# FPGA.net
KiCad netlist of a schematic drawn in Altium Designer
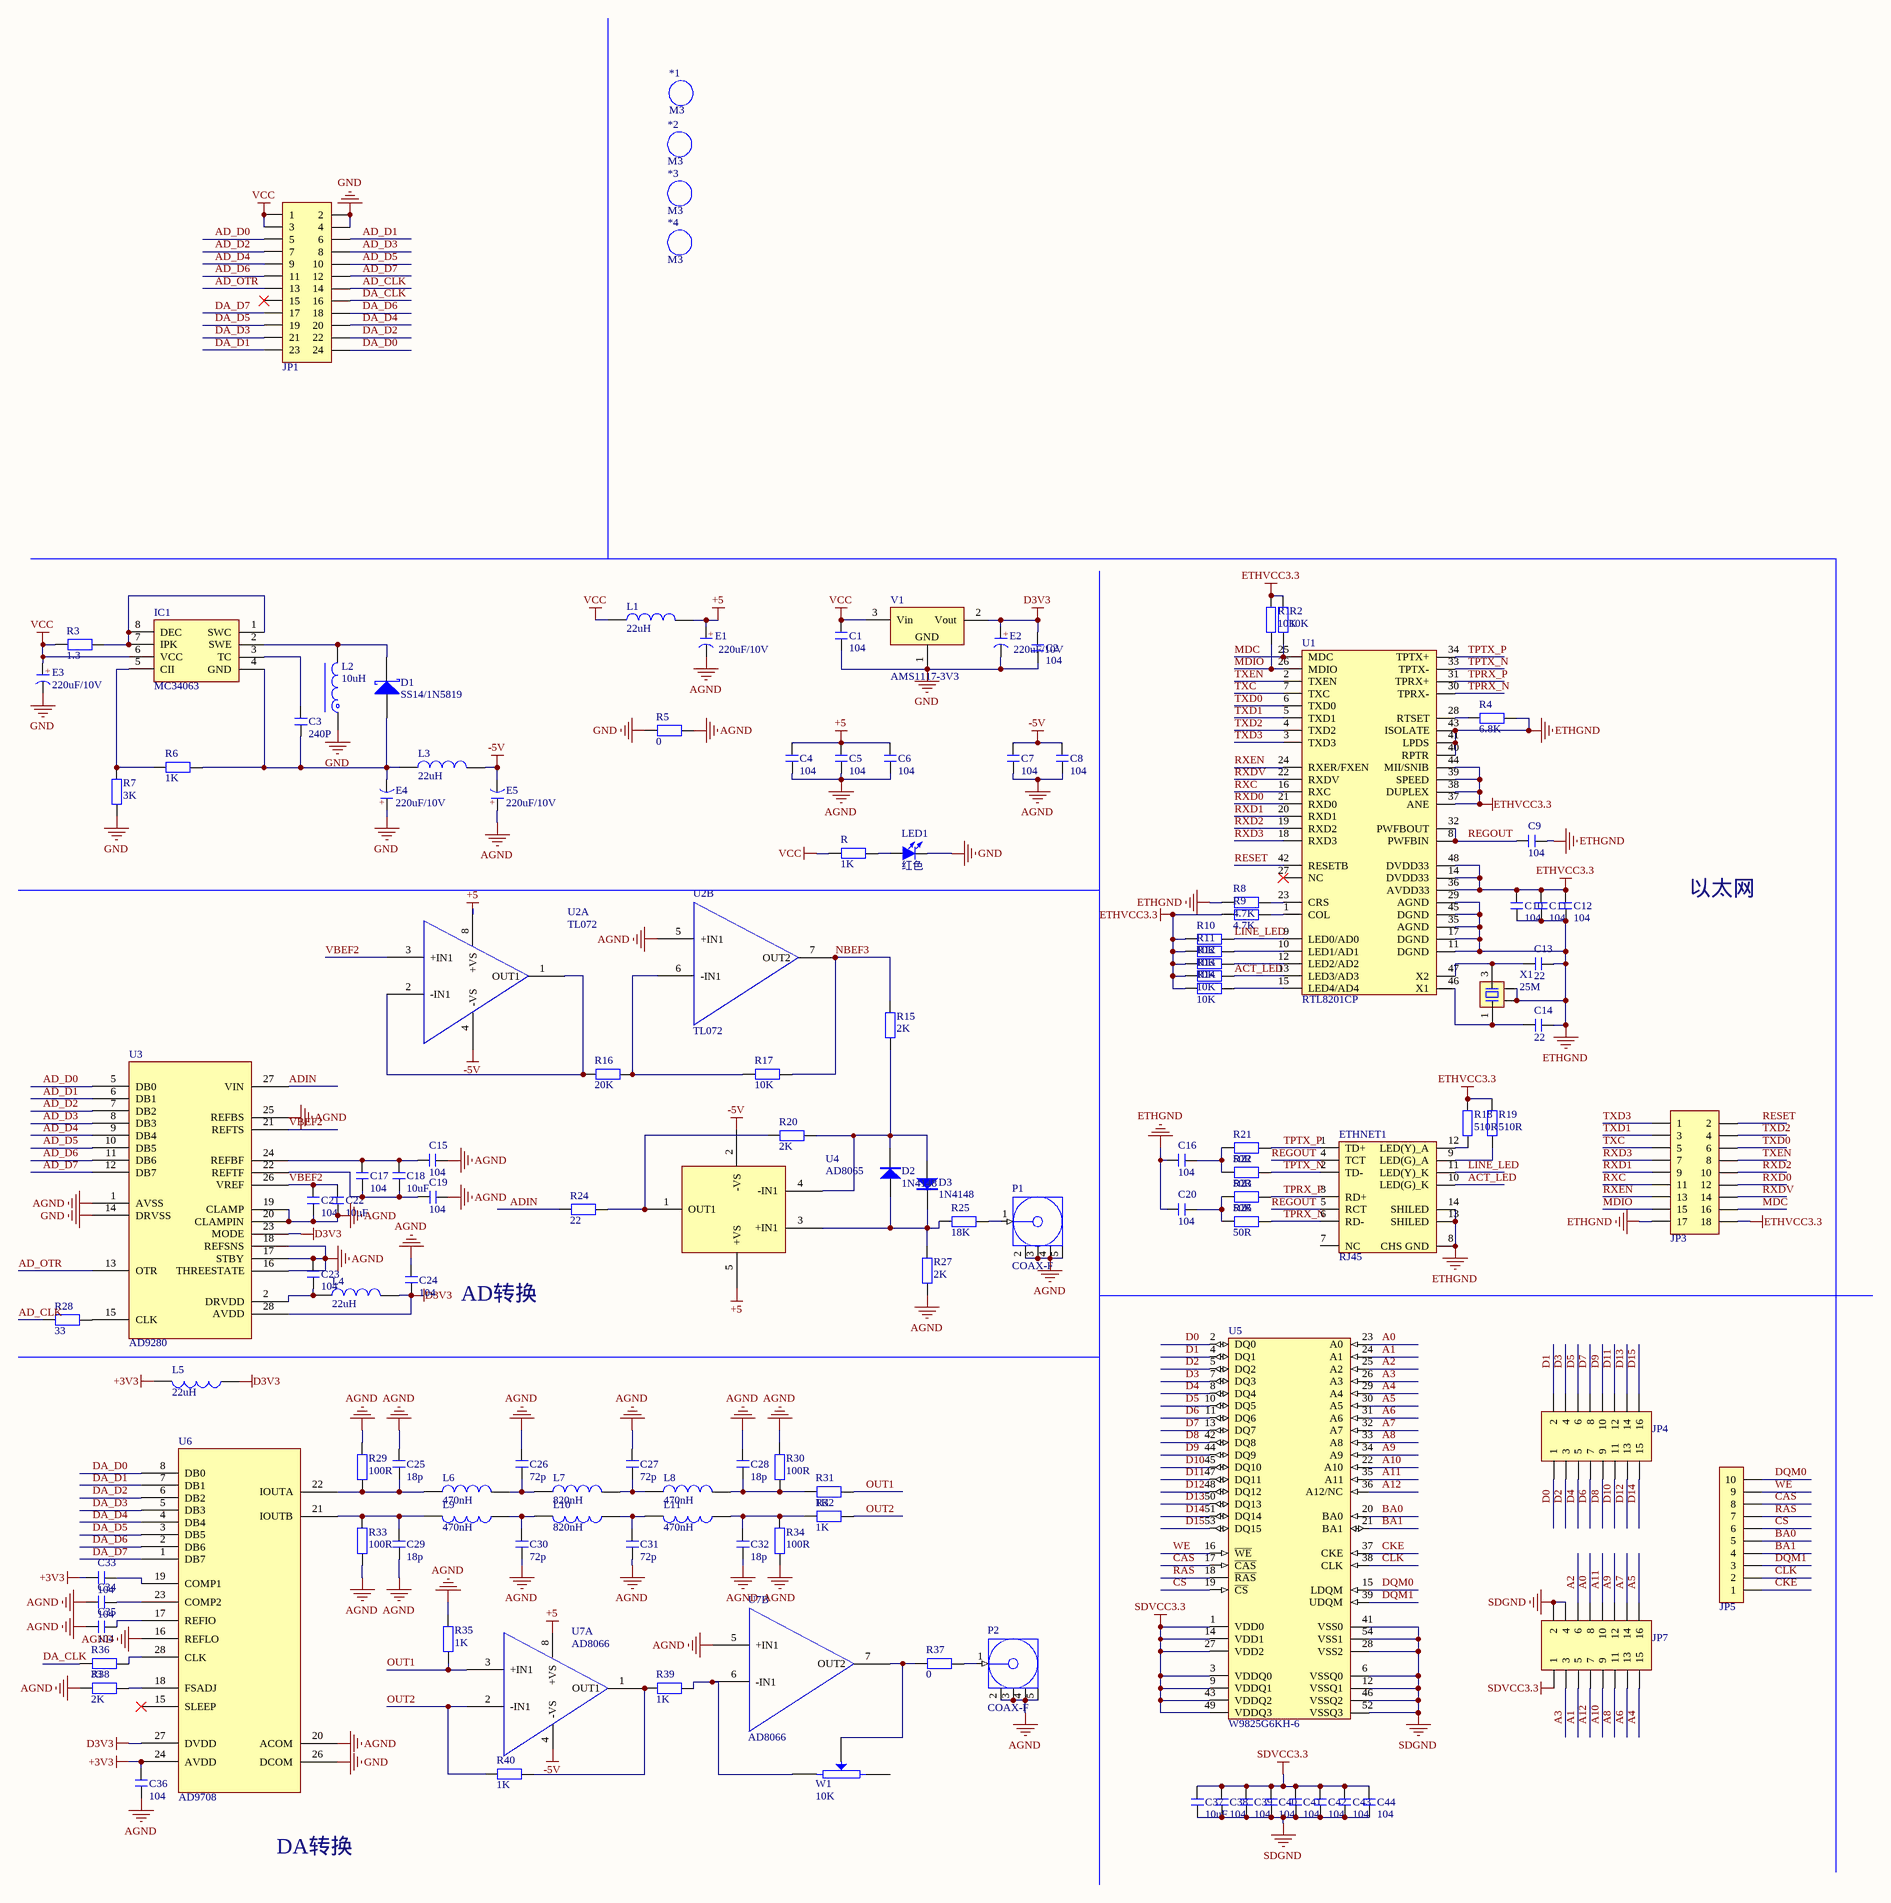
[diagram p0: FPGA扩展板.SchDoc]

(export (version "E")
  (design (tool "Eeschema 10.0.6"))
  (components
    (comp (ref "*1")
      (value "M3")
      (footprint "M3 125X300")
      (description "铜柱孔")
      (fields (field (name "版权归属") "封装库来自淘宝 ID：黄晶宝石"))
      (libsource (lib "4.1 - 未分类器件") (part "M3"))
    )
    (comp (ref "*2")
      (value "M3")
      (footprint "M3 125X300")
      (description "铜柱孔")
      (fields (field (name "版权归属") "封装库来自淘宝 ID：黄晶宝石"))
      (libsource (lib "4.1 - 未分类器件") (part "M3"))
    )
    (comp (ref "*3")
      (value "M3")
      (footprint "M3 125X300")
      (description "铜柱孔")
      (fields (field (name "版权归属") "封装库来自淘宝 ID：黄晶宝石"))
      (libsource (lib "4.1 - 未分类器件") (part "M3"))
    )
    (comp (ref "*4")
      (value "M3")
      (footprint "M3 125X300")
      (description "铜柱孔")
      (fields (field (name "版权归属") "封装库来自淘宝 ID：黄晶宝石"))
      (libsource (lib "4.1 - 未分类器件") (part "M3"))
    )
    (comp (ref "C1")
      (value "104")
      (footprint "C 0805_L")
      (description "贴片电容")
      (libsource (lib "0.1 - 电阻-电容-电感") (part "C"))
    )
    (comp (ref "C2")
      (value "104")
      (footprint "C 0805_L")
      (description "贴片电容")
      (libsource (lib "0.1 - 电阻-电容-电感") (part "C"))
    )
    (comp (ref "C3")
      (value "240P")
      (footprint "C 0805_L")
      (description "贴片电容")
      (libsource (lib "0.1 - 电阻-电容-电感") (part "C"))
    )
    (comp (ref "C4")
      (value "104")
      (footprint "C 0805_L")
      (description "贴片电容")
      (libsource (lib "0.1 - 电阻-电容-电感") (part "C"))
    )
    (comp (ref "C5")
      (value "104")
      (footprint "C 0805_L")
      (description "贴片电容")
      (libsource (lib "0.1 - 电阻-电容-电感") (part "C"))
    )
    (comp (ref "C6")
      (value "104")
      (footprint "C 0805_L")
      (description "贴片电容")
      (libsource (lib "0.1 - 电阻-电容-电感") (part "C"))
    )
    (comp (ref "C7")
      (value "104")
      (footprint "C 0805_L")
      (description "贴片电容")
      (libsource (lib "0.1 - 电阻-电容-电感") (part "C"))
    )
    (comp (ref "C8")
      (value "104")
      (footprint "C 0805_L")
      (description "贴片电容")
      (libsource (lib "0.1 - 电阻-电容-电感") (part "C"))
    )
    (comp (ref "C9")
      (value "104")
      (footprint "C 0805_L")
      (description "贴片电容")
      (libsource (lib "0.1 - 电阻-电容-电感") (part "C"))
    )
    (comp (ref "C10")
      (value "104")
      (footprint "C 0805_L")
      (description "贴片电容")
      (libsource (lib "0.1 - 电阻-电容-电感") (part "C"))
    )
    (comp (ref "C11")
      (value "104")
      (footprint "C 0805_L")
      (description "贴片电容")
      (libsource (lib "0.1 - 电阻-电容-电感") (part "C"))
    )
    (comp (ref "C12")
      (value "104")
      (footprint "C 0805_L")
      (description "贴片电容")
      (libsource (lib "0.1 - 电阻-电容-电感") (part "C"))
    )
    (comp (ref "C13")
      (value "22")
      (footprint "C 0805_L")
      (description "贴片电容")
      (libsource (lib "0.1 - 电阻-电容-电感") (part "C"))
    )
    (comp (ref "C14")
      (value "22")
      (footprint "C 0805_L")
      (description "贴片电容")
      (libsource (lib "0.1 - 电阻-电容-电感") (part "C"))
    )
    (comp (ref "C15")
      (value "104")
      (footprint "C 0805_L")
      (description "贴片电容")
      (libsource (lib "0.1 - 电阻-电容-电感") (part "C"))
    )
    (comp (ref "C16")
      (value "104")
      (footprint "C 0805_L")
      (description "贴片电容")
      (libsource (lib "0.1 - 电阻-电容-电感") (part "C"))
    )
    (comp (ref "C17")
      (value "104")
      (footprint "C 0805_L")
      (description "贴片电容")
      (libsource (lib "0.1 - 电阻-电容-电感") (part "C"))
    )
    (comp (ref "C18")
      (value "10uF")
      (footprint "C 0805_L")
      (description "贴片电容")
      (libsource (lib "0.1 - 电阻-电容-电感") (part "C"))
    )
    (comp (ref "C19")
      (value "104")
      (footprint "C 0805_L")
      (description "贴片电容")
      (libsource (lib "0.1 - 电阻-电容-电感") (part "C"))
    )
    (comp (ref "C20")
      (value "104")
      (footprint "C 0805_L")
      (description "贴片电容")
      (libsource (lib "0.1 - 电阻-电容-电感") (part "C"))
    )
    (comp (ref "C21")
      (value "104")
      (footprint "C 0805_L")
      (description "贴片电容")
      (libsource (lib "0.1 - 电阻-电容-电感") (part "C"))
    )
    (comp (ref "C22")
      (value "10uF")
      (footprint "C 0805_L")
      (description "贴片电容")
      (libsource (lib "0.1 - 电阻-电容-电感") (part "C"))
    )
    (comp (ref "C23")
      (value "104")
      (footprint "C 0805_L")
      (description "贴片电容")
      (libsource (lib "0.1 - 电阻-电容-电感") (part "C"))
    )
    (comp (ref "C24")
      (value "104")
      (footprint "C 0805_L")
      (description "贴片电容")
      (libsource (lib "0.1 - 电阻-电容-电感") (part "C"))
    )
    (comp (ref "C25")
      (value "18p")
      (footprint "C 0805_L")
      (description "贴片电容")
      (libsource (lib "0.1 - 电阻-电容-电感") (part "C"))
    )
    (comp (ref "C26")
      (value "72p")
      (footprint "C 0805_L")
      (description "贴片电容")
      (libsource (lib "0.1 - 电阻-电容-电感") (part "C"))
    )
    (comp (ref "C27")
      (value "72p")
      (footprint "C 0805_L")
      (description "贴片电容")
      (libsource (lib "0.1 - 电阻-电容-电感") (part "C"))
    )
    (comp (ref "C28")
      (value "18p")
      (footprint "C 0805_L")
      (description "贴片电容")
      (libsource (lib "0.1 - 电阻-电容-电感") (part "C"))
    )
    (comp (ref "C29")
      (value "18p")
      (footprint "C 0805_L")
      (description "贴片电容")
      (libsource (lib "0.1 - 电阻-电容-电感") (part "C"))
    )
    (comp (ref "C30")
      (value "72p")
      (footprint "C 0805_L")
      (description "贴片电容")
      (libsource (lib "0.1 - 电阻-电容-电感") (part "C"))
    )
    (comp (ref "C31")
      (value "72p")
      (footprint "C 0805_L")
      (description "贴片电容")
      (libsource (lib "0.1 - 电阻-电容-电感") (part "C"))
    )
    (comp (ref "C32")
      (value "18p")
      (footprint "C 0805_L")
      (description "贴片电容")
      (libsource (lib "0.1 - 电阻-电容-电感") (part "C"))
    )
    (comp (ref "C33")
      (value "104")
      (footprint "C 0805_L")
      (description "贴片电容")
      (libsource (lib "0.1 - 电阻-电容-电感") (part "C"))
    )
    (comp (ref "C34")
      (value "104")
      (footprint "C 0805_L")
      (description "贴片电容")
      (libsource (lib "0.1 - 电阻-电容-电感") (part "C"))
    )
    (comp (ref "C35")
      (value "104")
      (footprint "C 0805_L")
      (description "贴片电容")
      (libsource (lib "0.1 - 电阻-电容-电感") (part "C"))
    )
    (comp (ref "C36")
      (value "104")
      (footprint "C 0805_L")
      (description "贴片电容")
      (libsource (lib "0.1 - 电阻-电容-电感") (part "C"))
    )
    (comp (ref "C37")
      (value "10uF")
      (footprint "C 0805_L")
      (description "贴片电容")
      (libsource (lib "0.1 - 电阻-电容-电感") (part "C"))
    )
    (comp (ref "C38")
      (value "104")
      (footprint "C 0805_L")
      (description "贴片电容")
      (libsource (lib "0.1 - 电阻-电容-电感") (part "C"))
    )
    (comp (ref "C39")
      (value "104")
      (footprint "C 0805_L")
      (description "贴片电容")
      (libsource (lib "0.1 - 电阻-电容-电感") (part "C"))
    )
    (comp (ref "C40")
      (value "104")
      (footprint "C 0805_L")
      (description "贴片电容")
      (libsource (lib "0.1 - 电阻-电容-电感") (part "C"))
    )
    (comp (ref "C41")
      (value "104")
      (footprint "C 0805_L")
      (description "贴片电容")
      (libsource (lib "0.1 - 电阻-电容-电感") (part "C"))
    )
    (comp (ref "C42")
      (value "104")
      (footprint "C 0805_L")
      (description "贴片电容")
      (libsource (lib "0.1 - 电阻-电容-电感") (part "C"))
    )
    (comp (ref "C43")
      (value "104")
      (footprint "C 0805_L")
      (description "贴片电容")
      (libsource (lib "0.1 - 电阻-电容-电感") (part "C"))
    )
    (comp (ref "C44")
      (value "104")
      (footprint "C 0805_L")
      (description "贴片电容")
      (libsource (lib "0.1 - 电阻-电容-电感") (part "C"))
    )
    (comp (ref "D1")
      (value "SS14/1N5819")
      (footprint "SMA")
      (description "肖特基二极管")
      (libsource (lib "0.2 -  二极管-整流桥") (part "SS14"))
    )
    (comp (ref "D2")
      (value "1N4148")
      (footprint "MINI_MELF (LL34)")
      (description "开关二极管")
      (libsource (lib "0.2 -  二极管-整流桥") (part "1N4148"))
    )
    (comp (ref "D3")
      (value "1N4148")
      (footprint "MINI_MELF (LL34)")
      (description "开关二极管")
      (libsource (lib "0.2 -  二极管-整流桥") (part "1N4148"))
    )
    (comp (ref "E1")
      (value "220uF/10V")
      (footprint "CM D(6.3*5.4)")
      (description "贴片电解电容")
      (fields (field (name "版权归属") "封装库来自淘宝 ID：黄晶宝石"))
      (libsource (lib "0.1 - 电阻-电容-电感") (part "CE_SMD"))
    )
    (comp (ref "E2")
      (value "220uF/10V")
      (footprint "CM D(6.3*5.4)")
      (description "贴片电解电容")
      (fields (field (name "版权归属") "封装库来自淘宝 ID：黄晶宝石"))
      (libsource (lib "0.1 - 电阻-电容-电感") (part "CE_SMD"))
    )
    (comp (ref "E3")
      (value "220uF/10V")
      (footprint "CM D(6.3*5.4)")
      (description "贴片电解电容")
      (fields (field (name "版权归属") "封装库来自淘宝 ID：黄晶宝石"))
      (libsource (lib "0.1 - 电阻-电容-电感") (part "CE_SMD"))
    )
    (comp (ref "E4")
      (value "220uF/10V")
      (footprint "CM D(6.3*5.4)")
      (description "贴片电解电容")
      (fields (field (name "版权归属") "封装库来自淘宝 ID：黄晶宝石"))
      (libsource (lib "0.1 - 电阻-电容-电感") (part "CE_SMD"))
    )
    (comp (ref "E5")
      (value "220uF/10V")
      (footprint "CM D(6.3*5.4)")
      (description "贴片电解电容")
      (fields (field (name "版权归属") "封装库来自淘宝 ID：黄晶宝石"))
      (libsource (lib "0.1 - 电阻-电容-电感") (part "CE_SMD"))
    )
    (comp (ref "ETHNET1")
      (value "RJ45")
      (footprint "HR911105A")
      (libsource (lib "PIONEER") (part "HR911105"))
    )
    (comp (ref "IC1")
      (value "MC34063")
      (footprint "SOP8_N")
      (description "DC升降压芯片")
      (fields (field (name "版权归属") "封装库来自淘宝 ID：黄晶宝石"))
      (libsource (lib "1.1 - 电源类芯片") (part "MC34063"))
    )
    (comp (ref "JP1")
      (value "Header 2X11")
      (footprint "HDR2.54-LI-2x12P")
      (description "12*2P接插件")
      (fields (field (name "版权归属") "源创客"))
      (libsource (lib "5.3 - 接插件-脚距2.54 (100mil) ") (part "Header 12X2"))
    )
    (comp (ref "JP3")
      (value "Header 9X2")
      (footprint "HDR2.54-LI-2x9P")
      (description "9*2P接插件")
      (fields (field (name "版权归属") "源创客"))
      (libsource (lib "5.3 - 接插件-脚距2.54 (100mil) ") (part "Header 9X2"))
    )
    (comp (ref "JP4")
      (value "Header 8X2")
      (footprint "HDR2.54-LI-2x8P")
      (description "8*2P接插件")
      (fields (field (name "版权归属") "封装库来自淘宝 ID：黄晶宝石"))
      (libsource (lib "5.3 - 接插件-脚距2.54 (100mil) ") (part "Header 8X2"))
    )
    (comp (ref "JP5")
      (value "HDR-1X10")
      (footprint "HDR2.54-LI-10P")
      (description "10P接插件")
      (fields (field (name "版权归属") "源创客"))
      (libsource (lib "5.3 - 接插件-脚距2.54 (100mil) ") (part "Header 10"))
    )
    (comp (ref "JP7")
      (value "Header 8X2")
      (footprint "HDR2.54-LI-2x8P")
      (description "8*2P接插件")
      (fields (field (name "版权归属") "封装库来自淘宝 ID：黄晶宝石"))
      (libsource (lib "5.3 - 接插件-脚距2.54 (100mil) ") (part "Header 8X2"))
    )
    (comp (ref "L1")
      (value "22uH")
      (footprint "L 0805")
      (description "小功率贴片电感")
      (libsource (lib "0.1 - 电阻-电容-电感") (part "L"))
    )
    (comp (ref "L2")
      (value "10uH")
      (footprint "CDRH73")
      (description "功率屏蔽电感")
      (fields (field (name "版权归属") "封装库来自淘宝 ID：黄晶宝石"))
      (libsource (lib "0.1 - 电阻-电容-电感") (part "L-CDRH"))
    )
    (comp (ref "L3")
      (value "22uH")
      (footprint "L 0805")
      (description "小功率贴片电感")
      (libsource (lib "0.1 - 电阻-电容-电感") (part "L"))
    )
    (comp (ref "L4")
      (value "22uH")
      (footprint "L 0805")
      (description "小功率贴片电感")
      (libsource (lib "0.1 - 电阻-电容-电感") (part "L"))
    )
    (comp (ref "L5")
      (value "22uH")
      (footprint "L 0805")
      (description "小功率贴片电感")
      (libsource (lib "0.1 - 电阻-电容-电感") (part "L"))
    )
    (comp (ref "L6")
      (value "470nH")
      (footprint "L 0805")
      (description "小功率贴片电感")
      (libsource (lib "0.1 - 电阻-电容-电感") (part "L"))
    )
    (comp (ref "L7")
      (value "820nH")
      (footprint "L 0805")
      (description "小功率贴片电感")
      (libsource (lib "0.1 - 电阻-电容-电感") (part "L"))
    )
    (comp (ref "L8")
      (value "470nH")
      (footprint "L 0805")
      (description "小功率贴片电感")
      (libsource (lib "0.1 - 电阻-电容-电感") (part "L"))
    )
    (comp (ref "L9")
      (value "470nH")
      (footprint "L 0805")
      (description "小功率贴片电感")
      (libsource (lib "0.1 - 电阻-电容-电感") (part "L"))
    )
    (comp (ref "L10")
      (value "820nH")
      (footprint "L 0805")
      (description "小功率贴片电感")
      (libsource (lib "0.1 - 电阻-电容-电感") (part "L"))
    )
    (comp (ref "L11")
      (value "470nH")
      (footprint "L 0805")
      (description "小功率贴片电感")
      (libsource (lib "0.1 - 电阻-电容-电感") (part "L"))
    )
    (comp (ref "LED1")
      (value "红色")
      (footprint "LED 0805B")
      (description "贴片LED")
      (fields (field (name "版权归属") "封装库来自淘宝 ID：黄晶宝石"))
      (libsource (lib "0.3 - LED发光二极管") (part "LED-SMD"))
    )
    (comp (ref "P1")
      (value "COAX-F")
      (footprint "MCX5.08-H5")
      (fields (field (name "PUBLISHER") "Altium Limited"))
      (libsource (lib "HS_AD_DA_V2.3") (part "COAX-F"))
    )
    (comp (ref "P2")
      (value "COAX-F")
      (footprint "MCX5.08-H5")
      (fields (field (name "PUBLISHER") "Altium Limited"))
      (libsource (lib "HS_AD_DA_V2.3") (part "COAX-F"))
    )
    (comp (ref "R")
      (value "1K")
      (footprint "R 0805_L")
      (description "贴片电阻")
      (fields (field (name "版权归属") "来自淘宝 ID：黄晶宝石"))
      (libsource (lib "0.1 - 电阻-电容-电感") (part "R"))
    )
    (comp (ref "R1")
      (value "10K")
      (footprint "R 0805_L")
      (description "贴片电阻")
      (fields (field (name "版权归属") "来自淘宝 ID：黄晶宝石"))
      (libsource (lib "0.1 - 电阻-电容-电感") (part "R"))
    )
    (comp (ref "R2")
      (value "10K")
      (footprint "R 0805_L")
      (description "贴片电阻")
      (fields (field (name "版权归属") "来自淘宝 ID：黄晶宝石"))
      (libsource (lib "0.1 - 电阻-电容-电感") (part "R"))
    )
    (comp (ref "R3")
      (value "1.3")
      (footprint "R 0805_L")
      (description "贴片电阻")
      (fields (field (name "版权归属") "来自淘宝 ID：黄晶宝石"))
      (libsource (lib "0.1 - 电阻-电容-电感") (part "R"))
    )
    (comp (ref "R4")
      (value "6.8K")
      (footprint "R 0805_L")
      (description "贴片电阻")
      (fields (field (name "版权归属") "来自淘宝 ID：黄晶宝石"))
      (libsource (lib "0.1 - 电阻-电容-电感") (part "R"))
    )
    (comp (ref "R5")
      (value "0")
      (footprint "R 0805_L")
      (description "贴片电阻")
      (fields (field (name "版权归属") "来自淘宝 ID：黄晶宝石"))
      (libsource (lib "0.1 - 电阻-电容-电感") (part "R"))
    )
    (comp (ref "R6")
      (value "1K")
      (footprint "R 0805_L")
      (description "贴片电阻")
      (fields (field (name "版权归属") "来自淘宝 ID：黄晶宝石"))
      (libsource (lib "0.1 - 电阻-电容-电感") (part "R"))
    )
    (comp (ref "R7")
      (value "3K")
      (footprint "R 0805_L")
      (description "贴片电阻")
      (fields (field (name "版权归属") "来自淘宝 ID：黄晶宝石"))
      (libsource (lib "0.1 - 电阻-电容-电感") (part "R"))
    )
    (comp (ref "R8")
      (value "4.7K")
      (footprint "R 0805_L")
      (description "贴片电阻")
      (fields (field (name "版权归属") "来自淘宝 ID：黄晶宝石"))
      (libsource (lib "0.1 - 电阻-电容-电感") (part "R"))
    )
    (comp (ref "R9")
      (value "4.7K")
      (footprint "R 0805_L")
      (description "贴片电阻")
      (fields (field (name "版权归属") "来自淘宝 ID：黄晶宝石"))
      (libsource (lib "0.1 - 电阻-电容-电感") (part "R"))
    )
    (comp (ref "R10")
      (value "10K")
      (footprint "R 0805_L")
      (description "贴片电阻")
      (fields (field (name "版权归属") "来自淘宝 ID：黄晶宝石"))
      (libsource (lib "0.1 - 电阻-电容-电感") (part "R"))
    )
    (comp (ref "R11")
      (value "10K")
      (footprint "R 0805_L")
      (description "贴片电阻")
      (fields (field (name "版权归属") "来自淘宝 ID：黄晶宝石"))
      (libsource (lib "0.1 - 电阻-电容-电感") (part "R"))
    )
    (comp (ref "R12")
      (value "10K")
      (footprint "R 0805_L")
      (description "贴片电阻")
      (fields (field (name "版权归属") "来自淘宝 ID：黄晶宝石"))
      (libsource (lib "0.1 - 电阻-电容-电感") (part "R"))
    )
    (comp (ref "R13")
      (value "10K")
      (footprint "R 0805_L")
      (description "贴片电阻")
      (fields (field (name "版权归属") "来自淘宝 ID：黄晶宝石"))
      (libsource (lib "0.1 - 电阻-电容-电感") (part "R"))
    )
    (comp (ref "R14")
      (value "10K")
      (footprint "R 0805_L")
      (description "贴片电阻")
      (fields (field (name "版权归属") "来自淘宝 ID：黄晶宝石"))
      (libsource (lib "0.1 - 电阻-电容-电感") (part "R"))
    )
    (comp (ref "R15")
      (value "2K")
      (footprint "R 0805_L")
      (description "贴片电阻")
      (fields (field (name "版权归属") "来自淘宝 ID：黄晶宝石"))
      (libsource (lib "0.1 - 电阻-电容-电感") (part "R"))
    )
    (comp (ref "R16")
      (value "20K")
      (footprint "R 0805_L")
      (description "贴片电阻")
      (fields (field (name "版权归属") "来自淘宝 ID：黄晶宝石"))
      (libsource (lib "0.1 - 电阻-电容-电感") (part "R"))
    )
    (comp (ref "R17")
      (value "10K")
      (footprint "R 0805_L")
      (description "贴片电阻")
      (fields (field (name "版权归属") "来自淘宝 ID：黄晶宝石"))
      (libsource (lib "0.1 - 电阻-电容-电感") (part "R"))
    )
    (comp (ref "R18")
      (value "510R")
      (footprint "R 0805_L")
      (description "贴片电阻")
      (fields (field (name "版权归属") "来自淘宝 ID：黄晶宝石"))
      (libsource (lib "0.1 - 电阻-电容-电感") (part "R"))
    )
    (comp (ref "R19")
      (value "510R")
      (footprint "R 0805_L")
      (description "贴片电阻")
      (fields (field (name "版权归属") "来自淘宝 ID：黄晶宝石"))
      (libsource (lib "0.1 - 电阻-电容-电感") (part "R"))
    )
    (comp (ref "R20")
      (value "2K")
      (footprint "R 0805_L")
      (description "贴片电阻")
      (fields (field (name "版权归属") "来自淘宝 ID：黄晶宝石"))
      (libsource (lib "0.1 - 电阻-电容-电感") (part "R"))
    )
    (comp (ref "R21")
      (value "50R")
      (footprint "R 0805_L")
      (description "贴片电阻")
      (fields (field (name "版权归属") "来自淘宝 ID：黄晶宝石"))
      (libsource (lib "0.1 - 电阻-电容-电感") (part "R"))
    )
    (comp (ref "R22")
      (value "50R")
      (footprint "R 0805_L")
      (description "贴片电阻")
      (fields (field (name "版权归属") "来自淘宝 ID：黄晶宝石"))
      (libsource (lib "0.1 - 电阻-电容-电感") (part "R"))
    )
    (comp (ref "R23")
      (value "50R")
      (footprint "R 0805_L")
      (description "贴片电阻")
      (fields (field (name "版权归属") "来自淘宝 ID：黄晶宝石"))
      (libsource (lib "0.1 - 电阻-电容-电感") (part "R"))
    )
    (comp (ref "R24")
      (value "22")
      (footprint "R 0805_L")
      (description "贴片电阻")
      (fields (field (name "版权归属") "来自淘宝 ID：黄晶宝石"))
      (libsource (lib "0.1 - 电阻-电容-电感") (part "R"))
    )
    (comp (ref "R25")
      (value "18K")
      (footprint "R 0805_L")
      (description "贴片电阻")
      (fields (field (name "版权归属") "来自淘宝 ID：黄晶宝石"))
      (libsource (lib "0.1 - 电阻-电容-电感") (part "R"))
    )
    (comp (ref "R26")
      (value "50R")
      (footprint "R 0805_L")
      (description "贴片电阻")
      (fields (field (name "版权归属") "来自淘宝 ID：黄晶宝石"))
      (libsource (lib "0.1 - 电阻-电容-电感") (part "R"))
    )
    (comp (ref "R27")
      (value "2K")
      (footprint "R 0805_L")
      (description "贴片电阻")
      (fields (field (name "版权归属") "来自淘宝 ID：黄晶宝石"))
      (libsource (lib "0.1 - 电阻-电容-电感") (part "R"))
    )
    (comp (ref "R28")
      (value "33")
      (footprint "R 0805_L")
      (description "贴片电阻")
      (fields (field (name "版权归属") "来自淘宝 ID：黄晶宝石"))
      (libsource (lib "0.1 - 电阻-电容-电感") (part "R"))
    )
    (comp (ref "R29")
      (value "100R")
      (footprint "R 0805_L")
      (description "贴片电阻")
      (fields (field (name "版权归属") "来自淘宝 ID：黄晶宝石"))
      (libsource (lib "0.1 - 电阻-电容-电感") (part "R"))
    )
    (comp (ref "R30")
      (value "100R")
      (footprint "R 0805_L")
      (description "贴片电阻")
      (fields (field (name "版权归属") "来自淘宝 ID：黄晶宝石"))
      (libsource (lib "0.1 - 电阻-电容-电感") (part "R"))
    )
    (comp (ref "R31")
      (value "1K")
      (footprint "R 0805_L")
      (description "贴片电阻")
      (fields (field (name "版权归属") "来自淘宝 ID：黄晶宝石"))
      (libsource (lib "0.1 - 电阻-电容-电感") (part "R"))
    )
    (comp (ref "R32")
      (value "1K")
      (footprint "R 0805_L")
      (description "贴片电阻")
      (fields (field (name "版权归属") "来自淘宝 ID：黄晶宝石"))
      (libsource (lib "0.1 - 电阻-电容-电感") (part "R"))
    )
    (comp (ref "R33")
      (value "100R")
      (footprint "R 0805_L")
      (description "贴片电阻")
      (fields (field (name "版权归属") "来自淘宝 ID：黄晶宝石"))
      (libsource (lib "0.1 - 电阻-电容-电感") (part "R"))
    )
    (comp (ref "R34")
      (value "100R")
      (footprint "R 0805_L")
      (description "贴片电阻")
      (fields (field (name "版权归属") "来自淘宝 ID：黄晶宝石"))
      (libsource (lib "0.1 - 电阻-电容-电感") (part "R"))
    )
    (comp (ref "R35")
      (value "1K")
      (footprint "R 0805_L")
      (description "贴片电阻")
      (fields (field (name "版权归属") "来自淘宝 ID：黄晶宝石"))
      (libsource (lib "0.1 - 电阻-电容-电感") (part "R"))
    )
    (comp (ref "R36")
      (value "33")
      (footprint "R 0805_L")
      (description "贴片电阻")
      (fields (field (name "版权归属") "来自淘宝 ID：黄晶宝石"))
      (libsource (lib "0.1 - 电阻-电容-电感") (part "R"))
    )
    (comp (ref "R37")
      (value "0")
      (footprint "R 0805_L")
      (description "贴片电阻")
      (fields (field (name "版权归属") "来自淘宝 ID：黄晶宝石"))
      (libsource (lib "0.1 - 电阻-电容-电感") (part "R"))
    )
    (comp (ref "R38")
      (value "2K")
      (footprint "R 0805_L")
      (description "贴片电阻")
      (fields (field (name "版权归属") "来自淘宝 ID：黄晶宝石"))
      (libsource (lib "0.1 - 电阻-电容-电感") (part "R"))
    )
    (comp (ref "R39")
      (value "1K")
      (footprint "R 0805_L")
      (description "贴片电阻")
      (fields (field (name "版权归属") "来自淘宝 ID：黄晶宝石"))
      (libsource (lib "0.1 - 电阻-电容-电感") (part "R"))
    )
    (comp (ref "R40")
      (value "1K")
      (footprint "R 0805_L")
      (description "贴片电阻")
      (fields (field (name "版权归属") "来自淘宝 ID：黄晶宝石"))
      (libsource (lib "0.1 - 电阻-电容-电感") (part "R"))
    )
    (comp (ref "U1")
      (value "RTL8201CP")
      (footprint "lqfp48s")
      (description "ETH PHY")
      (libsource (lib "PIONEER") (part "RTL8201CP"))
    )
    (comp (ref "U2") (value "TL072") (footprint "SOIC8YG") (libsource (lib "HS_AD_DA_V2.3") (part "TL072")))
    (comp (ref "U3")
      (value "AD9280")
      (footprint "LC-SSOP-28_208mil")
      (libsource (lib "HS_AD_DA_V2.3") (part "AD9280"))
    )
    (comp (ref "U4") (value "AD8065") (footprint "SOT23-5") (libsource (lib "HS_AD_DA_V2.3") (part "AD8065")))
    (comp (ref "U5")
      (value "W9825G6KH-6")
      (footprint "TSOP54")
      (description "32MB SDRAM")
      (libsource (lib "PIONEER") (part "IS42S16160B"))
    )
    (comp (ref "U6") (value "AD9708") (footprint "TSOP28") (libsource (lib "HS_AD_DA_V2.3") (part "AD9708")))
    (comp (ref "U7") (value "AD8066") (footprint "SOIC8YG") (libsource (lib "HS_AD_DA_V2.3") (part "AD8066")))
    (comp (ref "V1")
      (value "AMS1117-3V3")
      (footprint "SOT223_N")
      (description "三端稳压芯片")
      (libsource (lib "1.1 - 电源类芯片") (part "AMS1117"))
    )
    (comp (ref "W1")
      (value "10K")
      (footprint "10K RW")
      (description "Potentiometer")
      (libsource (lib "HS_AD_DA_V2.3") (part "POT2"))
    )
    (comp (ref "X1")
      (value "25M")
      (footprint "OSC 3225-4P")
      (description "4脚无源晶振")
      (fields (field (name "版权归属") "源创客"))
      (libsource (lib "2.0 - 保险丝-晶振-光耦") (part "XTAL-4P"))
    )
  )
  (nets
    (net (code "1") (name "+3V3") (class "Default")
      (node (ref "C33") (pin "1") (pinfunction "1_1") (pintype "passive"))
      (node (ref "C36") (pin "1") (pinfunction "1_1") (pintype "passive"))
      (node (ref "L5") (pin "2") (pinfunction "2_2") (pintype "passive"))
      (node (ref "U6") (pin "24") (pinfunction "AVDD_24") (pintype "power_in"))
    )
    (net (code "2") (name "+5") (class "Default")
      (node (ref "C4") (pin "2") (pinfunction "2_2") (pintype "passive"))
      (node (ref "C5") (pin "2") (pinfunction "2_2") (pintype "passive"))
      (node (ref "C6") (pin "2") (pinfunction "2_2") (pintype "passive"))
      (node (ref "E1") (pin "1") (pinfunction "A_1") (pintype "passive"))
      (node (ref "L1") (pin "2") (pinfunction "2_2") (pintype "passive"))
      (node (ref "U2") (pin "8") (pinfunction "+VS_8") (pintype "power_in"))
      (node (ref "U4") (pin "5") (pinfunction "+VS_5") (pintype "power_in"))
      (node (ref "U7") (pin "8") (pinfunction "+VS_8") (pintype "power_in"))
    )
    (net (code "3") (name "-5V") (class "Default")
      (node (ref "C7") (pin "2") (pinfunction "2_2") (pintype "passive"))
      (node (ref "C8") (pin "2") (pinfunction "2_2") (pintype "passive"))
      (node (ref "E5") (pin "2") (pinfunction "K_2") (pintype "passive"))
      (node (ref "L3") (pin "2") (pinfunction "2_2") (pintype "passive"))
      (node (ref "U2") (pin "4") (pinfunction "-VS_4") (pintype "power_in"))
      (node (ref "U4") (pin "2") (pinfunction "-VS_2") (pintype "power_in"))
      (node (ref "U7") (pin "4") (pinfunction "-VS_4") (pintype "power_in"))
    )
    (net (code "4") (name "/A0") (class "Default")
      (node (ref "JP7") (pin "8") (pinfunction "8_8") (pintype "passive"))
      (node (ref "U5") (pin "23") (pinfunction "A0_23") (pintype "input"))
    )
    (net (code "5") (name "/A1") (class "Default")
      (node (ref "JP7") (pin "5") (pinfunction "5_5") (pintype "passive"))
      (node (ref "U5") (pin "24") (pinfunction "A1_24") (pintype "input"))
    )
    (net (code "6") (name "/A2") (class "Default")
      (node (ref "JP7") (pin "6") (pinfunction "6_6") (pintype "passive"))
      (node (ref "U5") (pin "25") (pinfunction "A2_25") (pintype "input"))
    )
    (net (code "7") (name "/A3") (class "Default")
      (node (ref "JP7") (pin "3") (pinfunction "3_3") (pintype "passive"))
      (node (ref "U5") (pin "26") (pinfunction "A3_26") (pintype "input"))
    )
    (net (code "8") (name "/A4") (class "Default")
      (node (ref "JP7") (pin "15") (pinfunction "15_15") (pintype "passive"))
      (node (ref "U5") (pin "29") (pinfunction "A4_29") (pintype "input"))
    )
    (net (code "9") (name "/A5") (class "Default")
      (node (ref "JP7") (pin "16") (pinfunction "16_16") (pintype "passive"))
      (node (ref "U5") (pin "30") (pinfunction "A5_30") (pintype "input"))
    )
    (net (code "10") (name "/A6") (class "Default")
      (node (ref "JP7") (pin "13") (pinfunction "13_13") (pintype "passive"))
      (node (ref "U5") (pin "31") (pinfunction "A6_31") (pintype "input"))
    )
    (net (code "11") (name "/A7") (class "Default")
      (node (ref "JP7") (pin "14") (pinfunction "14_14") (pintype "passive"))
      (node (ref "U5") (pin "32") (pinfunction "A7_32") (pintype "input"))
    )
    (net (code "12") (name "/A8") (class "Default")
      (node (ref "JP7") (pin "11") (pinfunction "11_11") (pintype "passive"))
      (node (ref "U5") (pin "33") (pinfunction "A8_33") (pintype "input"))
    )
    (net (code "13") (name "/A9") (class "Default")
      (node (ref "JP7") (pin "12") (pinfunction "12_12") (pintype "passive"))
      (node (ref "U5") (pin "34") (pinfunction "A9_34") (pintype "input"))
    )
    (net (code "14") (name "/A10") (class "Default")
      (node (ref "JP7") (pin "9") (pinfunction "9_9") (pintype "passive"))
      (node (ref "U5") (pin "22") (pinfunction "A10_22") (pintype "input"))
    )
    (net (code "15") (name "/A11") (class "Default")
      (node (ref "JP7") (pin "10") (pinfunction "10_10") (pintype "passive"))
      (node (ref "U5") (pin "35") (pinfunction "A11_35") (pintype "input"))
    )
    (net (code "16") (name "/A12") (class "Default")
      (node (ref "JP7") (pin "7") (pinfunction "7_7") (pintype "passive"))
      (node (ref "U5") (pin "36") (pinfunction "A12/NC_36") (pintype "input"))
    )
    (net (code "17") (name "/ACT_LED") (class "Default")
      (node (ref "ETHNET1") (pin "10") (pinfunction "LED(G)_K_10") (pintype "passive"))
      (node (ref "R13") (pin "2") (pinfunction "2_2") (pintype "passive"))
      (node (ref "U1") (pin "13") (pinfunction "LED3/AD3_13") (pintype "passive"))
    )
    (net (code "18") (name "/ADIN") (class "Default")
      (node (ref "R24") (pin "2") (pinfunction "2_2") (pintype "passive"))
      (node (ref "U3") (pin "27") (pinfunction "VIN_27") (pintype "power_in"))
    )
    (net (code "19") (name "/AD_CLK") (class "Default")
      (node (ref "JP1") (pin "14") (pinfunction "14_14") (pintype "passive"))
      (node (ref "R28") (pin "2") (pinfunction "2_2") (pintype "passive"))
    )
    (net (code "20") (name "/AD_D0") (class "Default")
      (node (ref "JP1") (pin "5") (pinfunction "5_5") (pintype "passive"))
      (node (ref "U3") (pin "5") (pinfunction "DB0_5") (pintype "power_in"))
    )
    (net (code "21") (name "/AD_D1") (class "Default")
      (node (ref "JP1") (pin "6") (pinfunction "6_6") (pintype "passive"))
      (node (ref "U3") (pin "6") (pinfunction "DB1_6") (pintype "power_in"))
    )
    (net (code "22") (name "/AD_D2") (class "Default")
      (node (ref "JP1") (pin "7") (pinfunction "7_7") (pintype "passive"))
      (node (ref "U3") (pin "7") (pinfunction "DB2_7") (pintype "power_in"))
    )
    (net (code "23") (name "/AD_D3") (class "Default")
      (node (ref "JP1") (pin "8") (pinfunction "8_8") (pintype "passive"))
      (node (ref "U3") (pin "8") (pinfunction "DB3_8") (pintype "power_in"))
    )
    (net (code "24") (name "/AD_D4") (class "Default")
      (node (ref "JP1") (pin "9") (pinfunction "9_9") (pintype "passive"))
      (node (ref "U3") (pin "9") (pinfunction "DB4_9") (pintype "power_in"))
    )
    (net (code "25") (name "/AD_D5") (class "Default")
      (node (ref "JP1") (pin "10") (pinfunction "10_10") (pintype "passive"))
      (node (ref "U3") (pin "10") (pinfunction "DB5_10") (pintype "power_in"))
    )
    (net (code "26") (name "/AD_D6") (class "Default")
      (node (ref "JP1") (pin "11") (pinfunction "11_11") (pintype "passive"))
      (node (ref "U3") (pin "11") (pinfunction "DB6_11") (pintype "power_in"))
    )
    (net (code "27") (name "/AD_D7") (class "Default")
      (node (ref "JP1") (pin "12") (pinfunction "12_12") (pintype "passive"))
      (node (ref "U3") (pin "12") (pinfunction "DB7_12") (pintype "power_in"))
    )
    (net (code "28") (name "/AD_OTR") (class "Default")
      (node (ref "JP1") (pin "13") (pinfunction "13_13") (pintype "passive"))
      (node (ref "U3") (pin "13") (pinfunction "OTR_13") (pintype "power_in"))
    )
    (net (code "29") (name "/BA0") (class "Default")
      (node (ref "JP5") (pin "5") (pinfunction "5_5") (pintype "passive"))
      (node (ref "U5") (pin "20") (pinfunction "BA0_20") (pintype "input"))
    )
    (net (code "30") (name "/BA1") (class "Default")
      (node (ref "JP5") (pin "4") (pinfunction "4_4") (pintype "passive"))
      (node (ref "U5") (pin "21") (pinfunction "BA1_21") (pintype "bidirectional"))
    )
    (net (code "31") (name "/CAS") (class "Default")
      (node (ref "JP5") (pin "8") (pinfunction "8_8") (pintype "passive"))
      (node (ref "U5") (pin "17") (pinfunction "~{CAS}_17") (pintype "input"))
    )
    (net (code "32") (name "/CKE") (class "Default")
      (node (ref "JP5") (pin "1") (pinfunction "1_1") (pintype "passive"))
      (node (ref "U5") (pin "37") (pinfunction "CKE_37") (pintype "input"))
    )
    (net (code "33") (name "/CLK") (class "Default")
      (node (ref "JP5") (pin "2") (pinfunction "2_2") (pintype "passive"))
      (node (ref "U5") (pin "38") (pinfunction "CLK_38") (pintype "input"))
    )
    (net (code "34") (name "/CS") (class "Default")
      (node (ref "JP5") (pin "6") (pinfunction "6_6") (pintype "passive"))
      (node (ref "U5") (pin "19") (pinfunction "~{CS}_19") (pintype "input"))
    )
    (net (code "35") (name "/D0") (class "Default")
      (node (ref "JP4") (pin "1") (pinfunction "1_1") (pintype "passive"))
      (node (ref "U5") (pin "2") (pinfunction "DQ0_2") (pintype "bidirectional"))
    )
    (net (code "36") (name "/D1") (class "Default")
      (node (ref "JP4") (pin "2") (pinfunction "2_2") (pintype "passive"))
      (node (ref "U5") (pin "4") (pinfunction "DQ1_4") (pintype "bidirectional"))
    )
    (net (code "37") (name "/D2") (class "Default")
      (node (ref "JP4") (pin "3") (pinfunction "3_3") (pintype "passive"))
      (node (ref "U5") (pin "5") (pinfunction "DQ2_5") (pintype "bidirectional"))
    )
    (net (code "38") (name "/D3") (class "Default")
      (node (ref "JP4") (pin "4") (pinfunction "4_4") (pintype "passive"))
      (node (ref "U5") (pin "7") (pinfunction "DQ3_7") (pintype "bidirectional"))
    )
    (net (code "39") (name "/D4") (class "Default")
      (node (ref "JP4") (pin "5") (pinfunction "5_5") (pintype "passive"))
      (node (ref "U5") (pin "8") (pinfunction "DQ4_8") (pintype "bidirectional"))
    )
    (net (code "40") (name "/D5") (class "Default")
      (node (ref "JP4") (pin "6") (pinfunction "6_6") (pintype "passive"))
      (node (ref "U5") (pin "10") (pinfunction "DQ5_10") (pintype "bidirectional"))
    )
    (net (code "41") (name "/D6") (class "Default")
      (node (ref "JP4") (pin "7") (pinfunction "7_7") (pintype "passive"))
      (node (ref "U5") (pin "11") (pinfunction "DQ6_11") (pintype "bidirectional"))
    )
    (net (code "42") (name "/D7") (class "Default")
      (node (ref "JP4") (pin "8") (pinfunction "8_8") (pintype "passive"))
      (node (ref "U5") (pin "13") (pinfunction "DQ7_13") (pintype "bidirectional"))
    )
    (net (code "43") (name "/D8") (class "Default")
      (node (ref "JP4") (pin "9") (pinfunction "9_9") (pintype "passive"))
      (node (ref "U5") (pin "42") (pinfunction "DQ8_42") (pintype "bidirectional"))
    )
    (net (code "44") (name "/D9") (class "Default")
      (node (ref "JP4") (pin "10") (pinfunction "10_10") (pintype "passive"))
      (node (ref "U5") (pin "44") (pinfunction "DQ9_44") (pintype "bidirectional"))
    )
    (net (code "45") (name "/D10") (class "Default")
      (node (ref "JP4") (pin "11") (pinfunction "11_11") (pintype "passive"))
      (node (ref "U5") (pin "45") (pinfunction "DQ10_45") (pintype "bidirectional"))
    )
    (net (code "46") (name "/D11") (class "Default")
      (node (ref "JP4") (pin "12") (pinfunction "12_12") (pintype "passive"))
      (node (ref "U5") (pin "47") (pinfunction "DQ11_47") (pintype "bidirectional"))
    )
    (net (code "47") (name "/D12") (class "Default")
      (node (ref "JP4") (pin "13") (pinfunction "13_13") (pintype "passive"))
      (node (ref "U5") (pin "48") (pinfunction "DQ12_48") (pintype "bidirectional"))
    )
    (net (code "48") (name "/D13") (class "Default")
      (node (ref "JP4") (pin "14") (pinfunction "14_14") (pintype "passive"))
      (node (ref "U5") (pin "50") (pinfunction "DQ13_50") (pintype "bidirectional"))
    )
    (net (code "49") (name "/D14") (class "Default")
      (node (ref "JP4") (pin "15") (pinfunction "15_15") (pintype "passive"))
      (node (ref "U5") (pin "51") (pinfunction "DQ14_51") (pintype "bidirectional"))
    )
    (net (code "50") (name "/D15") (class "Default")
      (node (ref "JP4") (pin "16") (pinfunction "16_16") (pintype "passive"))
      (node (ref "U5") (pin "53") (pinfunction "DQ15_53") (pintype "bidirectional"))
    )
    (net (code "51") (name "/DA_CLK") (class "Default")
      (node (ref "JP1") (pin "16") (pinfunction "16_16") (pintype "passive"))
      (node (ref "R36") (pin "2") (pinfunction "2_2") (pintype "passive"))
    )
    (net (code "52") (name "/DA_D0") (class "Default")
      (node (ref "JP1") (pin "24") (pinfunction "24_24") (pintype "passive"))
      (node (ref "U6") (pin "8") (pinfunction "DB0_8") (pintype "power_in"))
    )
    (net (code "53") (name "/DA_D1") (class "Default")
      (node (ref "JP1") (pin "23") (pinfunction "23_23") (pintype "passive"))
      (node (ref "U6") (pin "7") (pinfunction "DB1_7") (pintype "power_in"))
    )
    (net (code "54") (name "/DA_D2") (class "Default")
      (node (ref "JP1") (pin "22") (pinfunction "22_22") (pintype "passive"))
      (node (ref "U6") (pin "6") (pinfunction "DB2_6") (pintype "power_in"))
    )
    (net (code "55") (name "/DA_D3") (class "Default")
      (node (ref "JP1") (pin "21") (pinfunction "21_21") (pintype "passive"))
      (node (ref "U6") (pin "5") (pinfunction "DB3_5") (pintype "power_in"))
    )
    (net (code "56") (name "/DA_D4") (class "Default")
      (node (ref "JP1") (pin "20") (pinfunction "20_20") (pintype "passive"))
      (node (ref "U6") (pin "4") (pinfunction "DB4_4") (pintype "power_in"))
    )
    (net (code "57") (name "/DA_D5") (class "Default")
      (node (ref "JP1") (pin "19") (pinfunction "19_19") (pintype "passive"))
      (node (ref "U6") (pin "3") (pinfunction "DB5_3") (pintype "power_in"))
    )
    (net (code "58") (name "/DA_D6") (class "Default")
      (node (ref "JP1") (pin "18") (pinfunction "18_18") (pintype "passive"))
      (node (ref "U6") (pin "2") (pinfunction "DB6_2") (pintype "power_in"))
    )
    (net (code "59") (name "/DA_D7") (class "Default")
      (node (ref "JP1") (pin "17") (pinfunction "17_17") (pintype "passive"))
      (node (ref "U6") (pin "1") (pinfunction "DB7_1") (pintype "power_in"))
    )
    (net (code "60") (name "/DQM0") (class "Default")
      (node (ref "JP5") (pin "10") (pinfunction "10_10") (pintype "passive"))
      (node (ref "U5") (pin "15") (pinfunction "LDQM_15") (pintype "input"))
    )
    (net (code "61") (name "/DQM1") (class "Default")
      (node (ref "JP5") (pin "3") (pinfunction "3_3") (pintype "passive"))
      (node (ref "U5") (pin "39") (pinfunction "UDQM_39") (pintype "input"))
    )
    (net (code "62") (name "/LINE_LED") (class "Default")
      (node (ref "ETHNET1") (pin "11") (pinfunction "LED(Y)_K_11") (pintype "passive"))
      (node (ref "R10") (pin "2") (pinfunction "2_2") (pintype "passive"))
      (node (ref "U1") (pin "9") (pinfunction "LED0/AD0_9") (pintype "passive"))
    )
    (net (code "63") (name "/MDC") (class "Default")
      (node (ref "JP3") (pin "16") (pinfunction "16_16") (pintype "passive"))
      (node (ref "R2") (pin "1") (pinfunction "1_1") (pintype "passive"))
      (node (ref "U1") (pin "25") (pinfunction "MDC_25") (pintype "passive"))
    )
    (net (code "64") (name "/MDIO") (class "Default")
      (node (ref "JP3") (pin "15") (pinfunction "15_15") (pintype "passive"))
      (node (ref "R1") (pin "1") (pinfunction "1_1") (pintype "passive"))
      (node (ref "U1") (pin "26") (pinfunction "MDIO_26") (pintype "passive"))
    )
    (net (code "65") (name "/NBEF3") (class "Default")
      (node (ref "R15") (pin "2") (pinfunction "2_2") (pintype "passive"))
      (node (ref "R17") (pin "1") (pinfunction "1_1") (pintype "passive"))
      (node (ref "U2") (pin "7") (pinfunction "OUT2_7") (pintype "power_in"))
    )
    (net (code "66") (name "/OUT1") (class "Default")
      (node (ref "R31") (pin "2") (pinfunction "2_2") (pintype "passive"))
      (node (ref "R35") (pin "1") (pinfunction "1_1") (pintype "passive"))
      (node (ref "U7") (pin "3") (pinfunction "+IN1_3") (pintype "power_in"))
    )
    (net (code "67") (name "/OUT2") (class "Default")
      (node (ref "R32") (pin "2") (pinfunction "2_2") (pintype "passive"))
      (node (ref "R40") (pin "2") (pinfunction "2_2") (pintype "passive"))
      (node (ref "U7") (pin "2") (pinfunction "-IN1_2") (pintype "power_in"))
    )
    (net (code "68") (name "/RAS") (class "Default")
      (node (ref "JP5") (pin "7") (pinfunction "7_7") (pintype "passive"))
      (node (ref "U5") (pin "18") (pinfunction "~{RAS}_18") (pintype "passive"))
    )
    (net (code "69") (name "/REGOUT") (class "Default")
      (node (ref "C9") (pin "2") (pinfunction "2_2") (pintype "passive"))
      (node (ref "ETHNET1") (pin "4") (pinfunction "TCT_4") (pintype "passive"))
      (node (ref "ETHNET1") (pin "5") (pinfunction "RCT_5") (pintype "passive"))
      (node (ref "U1") (pin "32") (pinfunction "PWFBOUT_32") (pintype "passive"))
      (node (ref "U1") (pin "8") (pinfunction "PWFBIN_8") (pintype "passive"))
    )
    (net (code "70") (name "/RESET") (class "Default")
      (node (ref "JP3") (pin "2") (pinfunction "2_2") (pintype "passive"))
      (node (ref "U1") (pin "42") (pinfunction "RESETB_42") (pintype "passive"))
    )
    (net (code "71") (name "/RXC") (class "Default")
      (node (ref "JP3") (pin "11") (pinfunction "11_11") (pintype "passive"))
      (node (ref "U1") (pin "16") (pinfunction "RXC_16") (pintype "passive"))
    )
    (net (code "72") (name "/RXD0") (class "Default")
      (node (ref "JP3") (pin "12") (pinfunction "12_12") (pintype "passive"))
      (node (ref "U1") (pin "21") (pinfunction "RXD0_21") (pintype "passive"))
    )
    (net (code "73") (name "/RXD1") (class "Default")
      (node (ref "JP3") (pin "9") (pinfunction "9_9") (pintype "passive"))
      (node (ref "U1") (pin "20") (pinfunction "RXD1_20") (pintype "passive"))
    )
    (net (code "74") (name "/RXD2") (class "Default")
      (node (ref "JP3") (pin "10") (pinfunction "10_10") (pintype "passive"))
      (node (ref "U1") (pin "19") (pinfunction "RXD2_19") (pintype "passive"))
    )
    (net (code "75") (name "/RXD3") (class "Default")
      (node (ref "JP3") (pin "7") (pinfunction "7_7") (pintype "passive"))
      (node (ref "U1") (pin "18") (pinfunction "RXD3_18") (pintype "passive"))
    )
    (net (code "76") (name "/RXDV") (class "Default")
      (node (ref "JP3") (pin "14") (pinfunction "14_14") (pintype "passive"))
      (node (ref "U1") (pin "22") (pinfunction "RXDV_22") (pintype "passive"))
    )
    (net (code "77") (name "/RXEN") (class "Default")
      (node (ref "JP3") (pin "13") (pinfunction "13_13") (pintype "passive"))
      (node (ref "U1") (pin "24") (pinfunction "RXER/FXEN_24") (pintype "passive"))
    )
    (net (code "78") (name "/TPRX_N") (class "Default")
      (node (ref "ETHNET1") (pin "6") (pinfunction "RD-_6") (pintype "passive"))
      (node (ref "R26") (pin "2") (pinfunction "2_2") (pintype "passive"))
      (node (ref "U1") (pin "30") (pinfunction "TPRX-_30") (pintype "passive"))
    )
    (net (code "79") (name "/TPRX_P") (class "Default")
      (node (ref "ETHNET1") (pin "3") (pinfunction "RD+_3") (pintype "passive"))
      (node (ref "R23") (pin "2") (pinfunction "2_2") (pintype "passive"))
      (node (ref "U1") (pin "31") (pinfunction "TPRX+_31") (pintype "passive"))
    )
    (net (code "80") (name "/TPTX_N") (class "Default")
      (node (ref "ETHNET1") (pin "2") (pinfunction "TD-_2") (pintype "passive"))
      (node (ref "R22") (pin "2") (pinfunction "2_2") (pintype "passive"))
      (node (ref "U1") (pin "33") (pinfunction "TPTX-_33") (pintype "passive"))
    )
    (net (code "81") (name "/TPTX_P") (class "Default")
      (node (ref "ETHNET1") (pin "1") (pinfunction "TD+_1") (pintype "passive"))
      (node (ref "R21") (pin "2") (pinfunction "2_2") (pintype "passive"))
      (node (ref "U1") (pin "34") (pinfunction "TPTX+_34") (pintype "passive"))
    )
    (net (code "82") (name "/TXC") (class "Default")
      (node (ref "JP3") (pin "5") (pinfunction "5_5") (pintype "passive"))
      (node (ref "U1") (pin "7") (pinfunction "TXC_7") (pintype "passive"))
    )
    (net (code "83") (name "/TXD0") (class "Default")
      (node (ref "JP3") (pin "6") (pinfunction "6_6") (pintype "passive"))
      (node (ref "U1") (pin "6") (pinfunction "TXD0_6") (pintype "passive"))
    )
    (net (code "84") (name "/TXD1") (class "Default")
      (node (ref "JP3") (pin "3") (pinfunction "3_3") (pintype "passive"))
      (node (ref "U1") (pin "5") (pinfunction "TXD1_5") (pintype "passive"))
    )
    (net (code "85") (name "/TXD2") (class "Default")
      (node (ref "JP3") (pin "4") (pinfunction "4_4") (pintype "passive"))
      (node (ref "U1") (pin "4") (pinfunction "TXD2_4") (pintype "passive"))
    )
    (net (code "86") (name "/TXD3") (class "Default")
      (node (ref "JP3") (pin "1") (pinfunction "1_1") (pintype "passive"))
      (node (ref "U1") (pin "3") (pinfunction "TXD3_3") (pintype "passive"))
    )
    (net (code "87") (name "/TXEN") (class "Default")
      (node (ref "JP3") (pin "8") (pinfunction "8_8") (pintype "passive"))
      (node (ref "U1") (pin "2") (pinfunction "TXEN_2") (pintype "passive"))
    )
    (net (code "88") (name "/VBEF2") (class "Default")
      (node (ref "C21") (pin "2") (pinfunction "2_2") (pintype "passive"))
      (node (ref "C22") (pin "2") (pinfunction "2_2") (pintype "passive"))
      (node (ref "U2") (pin "3") (pinfunction "+IN1_3") (pintype "power_in"))
      (node (ref "U3") (pin "21") (pinfunction "REFTS_21") (pintype "power_in"))
      (node (ref "U3") (pin "26") (pinfunction "VREF_26") (pintype "power_in"))
    )
    (net (code "89") (name "/WE") (class "Default")
      (node (ref "JP5") (pin "9") (pinfunction "9_9") (pintype "passive"))
      (node (ref "U5") (pin "16") (pinfunction "~{WE}_16") (pintype "input"))
    )
    (net (code "90") (name "AGND") (class "Default")
      (node (ref "C15") (pin "1") (pinfunction "1_1") (pintype "passive"))
      (node (ref "C19") (pin "2") (pinfunction "2_2") (pintype "passive"))
      (node (ref "C21") (pin "1") (pinfunction "1_1") (pintype "passive"))
      (node (ref "C22") (pin "1") (pinfunction "1_1") (pintype "passive"))
      (node (ref "C23") (pin "2") (pinfunction "2_2") (pintype "passive"))
      (node (ref "C24") (pin "1") (pinfunction "1_1") (pintype "passive"))
      (node (ref "C25") (pin "1") (pinfunction "1_1") (pintype "passive"))
      (node (ref "C26") (pin "1") (pinfunction "1_1") (pintype "passive"))
      (node (ref "C27") (pin "1") (pinfunction "1_1") (pintype "passive"))
      (node (ref "C28") (pin "1") (pinfunction "1_1") (pintype "passive"))
      (node (ref "C29") (pin "1") (pinfunction "1_1") (pintype "passive"))
      (node (ref "C30") (pin "1") (pinfunction "1_1") (pintype "passive"))
      (node (ref "C31") (pin "1") (pinfunction "1_1") (pintype "passive"))
      (node (ref "C32") (pin "1") (pinfunction "1_1") (pintype "passive"))
      (node (ref "C34") (pin "1") (pinfunction "1_1") (pintype "passive"))
      (node (ref "C35") (pin "1") (pinfunction "1_1") (pintype "passive"))
      (node (ref "C36") (pin "2") (pinfunction "2_2") (pintype "passive"))
      (node (ref "C4") (pin "1") (pinfunction "1_1") (pintype "passive"))
      (node (ref "C5") (pin "1") (pinfunction "1_1") (pintype "passive"))
      (node (ref "C6") (pin "1") (pinfunction "1_1") (pintype "passive"))
      (node (ref "C7") (pin "1") (pinfunction "1_1") (pintype "passive"))
      (node (ref "C8") (pin "1") (pinfunction "1_1") (pintype "passive"))
      (node (ref "E1") (pin "2") (pinfunction "K_2") (pintype "passive"))
      (node (ref "E5") (pin "1") (pinfunction "A_1") (pintype "passive"))
      (node (ref "P1") (pin "2") (pinfunction "GND_2") (pintype "power_in"))
      (node (ref "P1") (pin "3") (pinfunction "GND_3") (pintype "power_in"))
      (node (ref "P1") (pin "4") (pinfunction "GND_4") (pintype "power_in"))
      (node (ref "P1") (pin "5") (pinfunction "GND_5") (pintype "power_in"))
      (node (ref "P2") (pin "2") (pinfunction "GND_2") (pintype "power_in"))
      (node (ref "P2") (pin "3") (pinfunction "GND_3") (pintype "power_in"))
      (node (ref "P2") (pin "4") (pinfunction "GND_4") (pintype "power_in"))
      (node (ref "P2") (pin "5") (pinfunction "GND_5") (pintype "power_in"))
      (node (ref "R27") (pin "1") (pinfunction "1_1") (pintype "passive"))
      (node (ref "R29") (pin "1") (pinfunction "1_1") (pintype "passive"))
      (node (ref "R30") (pin "1") (pinfunction "1_1") (pintype "passive"))
      (node (ref "R33") (pin "2") (pinfunction "2_2") (pintype "passive"))
      (node (ref "R34") (pin "2") (pinfunction "2_2") (pintype "passive"))
      (node (ref "R35") (pin "2") (pinfunction "2_2") (pintype "passive"))
      (node (ref "R38") (pin "2") (pinfunction "2_2") (pintype "passive"))
      (node (ref "R5") (pin "1") (pinfunction "1_1") (pintype "passive"))
      (node (ref "U2") (pin "5") (pinfunction "+IN1_5") (pintype "power_in"))
      (node (ref "U3") (pin "1") (pinfunction "AVSS_1") (pintype "power_in"))
      (node (ref "U3") (pin "16") (pinfunction "THREESTATE_16") (pintype "power_in"))
      (node (ref "U3") (pin "17") (pinfunction "STBY_17") (pintype "power_in"))
      (node (ref "U3") (pin "18") (pinfunction "REFSNS_18") (pintype "power_in"))
      (node (ref "U3") (pin "19") (pinfunction "CLAMP_19") (pintype "power_in"))
      (node (ref "U3") (pin "20") (pinfunction "CLAMPIN_20") (pintype "power_in"))
      (node (ref "U3") (pin "25") (pinfunction "REFBS_25") (pintype "power_in"))
      (node (ref "U6") (pin "16") (pinfunction "REFLO_16") (pintype "power_in"))
      (node (ref "U6") (pin "20") (pinfunction "ACOM_20") (pintype "power_in"))
      (node (ref "U7") (pin "5") (pinfunction "+IN1_5") (pintype "power_in"))
    )
    (net (code "91") (name "D3V3") (class "Default")
      (node (ref "C2") (pin "2") (pinfunction "2_2") (pintype "passive"))
      (node (ref "C24") (pin "2") (pinfunction "2_2") (pintype "passive"))
      (node (ref "E2") (pin "1") (pinfunction "A_1") (pintype "passive"))
      (node (ref "L4") (pin "2") (pinfunction "2_2") (pintype "passive"))
      (node (ref "L5") (pin "1") (pinfunction "1_1") (pintype "passive"))
      (node (ref "U3") (pin "23") (pinfunction "MODE_23") (pintype "power_in"))
      (node (ref "U3") (pin "28") (pinfunction "AVDD_28") (pintype "power_in"))
      (node (ref "U6") (pin "27") (pinfunction "DVDD_27") (pintype "power_in"))
      (node (ref "V1") (pin "2") (pinfunction "Vout_2") (pintype "passive"))
    )
    (net (code "92") (name "ETHGND") (class "Default")
      (node (ref "C10") (pin "1") (pinfunction "1_1") (pintype "passive"))
      (node (ref "C11") (pin "1") (pinfunction "1_1") (pintype "passive"))
      (node (ref "C12") (pin "1") (pinfunction "1_1") (pintype "passive"))
      (node (ref "C13") (pin "2") (pinfunction "2_2") (pintype "passive"))
      (node (ref "C14") (pin "2") (pinfunction "2_2") (pintype "passive"))
      (node (ref "C16") (pin "2") (pinfunction "2_2") (pintype "passive"))
      (node (ref "C20") (pin "2") (pinfunction "2_2") (pintype "passive"))
      (node (ref "C9") (pin "1") (pinfunction "1_1") (pintype "passive"))
      (node (ref "ETHNET1") (pin "13") (pinfunction "SHILED_13") (pintype "passive"))
      (node (ref "ETHNET1") (pin "14") (pinfunction "SHILED_14") (pintype "passive"))
      (node (ref "ETHNET1") (pin "8") (pinfunction "CHS_GND_8") (pintype "passive"))
      (node (ref "JP3") (pin "17") (pinfunction "17_17") (pintype "passive"))
      (node (ref "R4") (pin "2") (pinfunction "2_2") (pintype "passive"))
      (node (ref "R8") (pin "1") (pinfunction "1_1") (pintype "passive"))
      (node (ref "U1") (pin "11") (pinfunction "DGND_11") (pintype "passive"))
      (node (ref "U1") (pin "17") (pinfunction "DGND_17") (pintype "passive"))
      (node (ref "U1") (pin "29") (pinfunction "AGND_29") (pintype "passive"))
      (node (ref "U1") (pin "35") (pinfunction "AGND_35") (pintype "passive"))
      (node (ref "U1") (pin "40") (pinfunction "RPTR_40") (pintype "passive"))
      (node (ref "U1") (pin "41") (pinfunction "LPDS_41") (pintype "passive"))
      (node (ref "U1") (pin "43") (pinfunction "ISOLATE_43") (pintype "passive"))
      (node (ref "U1") (pin "45") (pinfunction "DGND_45") (pintype "passive"))
      (node (ref "X1") (pin "2") (pinfunction "2_2") (pintype "passive"))
      (node (ref "X1") (pin "4") (pinfunction "4_4") (pintype "passive"))
    )
    (net (code "93") (name "ETHVCC3.3") (class "Default")
      (node (ref "C10") (pin "2") (pinfunction "2_2") (pintype "passive"))
      (node (ref "C11") (pin "2") (pinfunction "2_2") (pintype "passive"))
      (node (ref "C12") (pin "2") (pinfunction "2_2") (pintype "passive"))
      (node (ref "JP3") (pin "18") (pinfunction "18_18") (pintype "passive"))
      (node (ref "R1") (pin "2") (pinfunction "2_2") (pintype "passive"))
      (node (ref "R10") (pin "1") (pinfunction "1_1") (pintype "passive"))
      (node (ref "R11") (pin "1") (pinfunction "1_1") (pintype "passive"))
      (node (ref "R12") (pin "1") (pinfunction "1_1") (pintype "passive"))
      (node (ref "R13") (pin "1") (pinfunction "1_1") (pintype "passive"))
      (node (ref "R14") (pin "1") (pinfunction "1_1") (pintype "passive"))
      (node (ref "R18") (pin "2") (pinfunction "2_2") (pintype "passive"))
      (node (ref "R19") (pin "2") (pinfunction "2_2") (pintype "passive"))
      (node (ref "R2") (pin "2") (pinfunction "2_2") (pintype "passive"))
      (node (ref "R9") (pin "1") (pinfunction "1_1") (pintype "passive"))
      (node (ref "U1") (pin "14") (pinfunction "DVDD33_14") (pintype "passive"))
      (node (ref "U1") (pin "36") (pinfunction "AVDD33_36") (pintype "passive"))
      (node (ref "U1") (pin "37") (pinfunction "ANE_37") (pintype "passive"))
      (node (ref "U1") (pin "38") (pinfunction "DUPLEX_38") (pintype "passive"))
      (node (ref "U1") (pin "39") (pinfunction "SPEED_39") (pintype "passive"))
      (node (ref "U1") (pin "44") (pinfunction "MII/SNIB_44") (pintype "passive"))
      (node (ref "U1") (pin "48") (pinfunction "DVDD33_48") (pintype "passive"))
    )
    (net (code "94") (name "GND") (class "Default")
      (node (ref "C1") (pin "1") (pinfunction "1_1") (pintype "passive"))
      (node (ref "C2") (pin "1") (pinfunction "1_1") (pintype "passive"))
      (node (ref "E2") (pin "2") (pinfunction "K_2") (pintype "passive"))
      (node (ref "E3") (pin "2") (pinfunction "K_2") (pintype "passive"))
      (node (ref "E4") (pin "1") (pinfunction "A_1") (pintype "passive"))
      (node (ref "JP1") (pin "2") (pinfunction "2_2") (pintype "passive"))
      (node (ref "JP1") (pin "4") (pinfunction "4_4") (pintype "passive"))
      (node (ref "L2") (pin "1") (pinfunction "1_1") (pintype "passive"))
      (node (ref "LED1") (pin "2") (pinfunction "K_2") (pintype "passive"))
      (node (ref "R5") (pin "2") (pinfunction "2_2") (pintype "passive"))
      (node (ref "R7") (pin "1") (pinfunction "1_1") (pintype "passive"))
      (node (ref "U3") (pin "14") (pinfunction "DRVSS_14") (pintype "power_in"))
      (node (ref "U6") (pin "26") (pinfunction "DCOM_26") (pintype "power_in"))
      (node (ref "V1") (pin "1") (pinfunction "GND_1") (pintype "passive"))
    )
    (net (code "95") (name "Net-(C16-Pad1)") (class "Default")
      (node (ref "C16") (pin "1") (pinfunction "1_1") (pintype "passive"))
      (node (ref "R21") (pin "1") (pinfunction "1_1") (pintype "passive"))
      (node (ref "R22") (pin "1") (pinfunction "1_1") (pintype "passive"))
    )
    (net (code "96") (name "Net-(C20-Pad1)") (class "Default")
      (node (ref "C20") (pin "1") (pinfunction "1_1") (pintype "passive"))
      (node (ref "R23") (pin "1") (pinfunction "1_1") (pintype "passive"))
      (node (ref "R26") (pin "1") (pinfunction "1_1") (pintype "passive"))
    )
    (net (code "97") (name "Net-(C26-Pad2)") (class "Default")
      (node (ref "C26") (pin "2") (pinfunction "2_2") (pintype "passive"))
      (node (ref "L6") (pin "2") (pinfunction "2_2") (pintype "passive"))
      (node (ref "L7") (pin "1") (pinfunction "1_1") (pintype "passive"))
    )
    (net (code "98") (name "Net-(C27-Pad2)") (class "Default")
      (node (ref "C27") (pin "2") (pinfunction "2_2") (pintype "passive"))
      (node (ref "L7") (pin "2") (pinfunction "2_2") (pintype "passive"))
      (node (ref "L8") (pin "1") (pinfunction "1_1") (pintype "passive"))
    )
    (net (code "99") (name "Net-(C28-Pad2)") (class "Default")
      (node (ref "C28") (pin "2") (pinfunction "2_2") (pintype "passive"))
      (node (ref "L8") (pin "2") (pinfunction "2_2") (pintype "passive"))
      (node (ref "R30") (pin "2") (pinfunction "2_2") (pintype "passive"))
      (node (ref "R31") (pin "1") (pinfunction "1_1") (pintype "passive"))
    )
    (net (code "100") (name "Net-(C30-Pad2)") (class "Default")
      (node (ref "C30") (pin "2") (pinfunction "2_2") (pintype "passive"))
      (node (ref "L10") (pin "2") (pinfunction "2_2") (pintype "passive"))
      (node (ref "L9") (pin "1") (pinfunction "1_1") (pintype "passive"))
    )
    (net (code "101") (name "Net-(C31-Pad2)") (class "Default")
      (node (ref "C31") (pin "2") (pinfunction "2_2") (pintype "passive"))
      (node (ref "L10") (pin "1") (pinfunction "1_1") (pintype "passive"))
      (node (ref "L11") (pin "2") (pinfunction "2_2") (pintype "passive"))
    )
    (net (code "102") (name "Net-(C32-Pad2)") (class "Default")
      (node (ref "C32") (pin "2") (pinfunction "2_2") (pintype "passive"))
      (node (ref "L11") (pin "1") (pinfunction "1_1") (pintype "passive"))
      (node (ref "R32") (pin "1") (pinfunction "1_1") (pintype "passive"))
      (node (ref "R34") (pin "1") (pinfunction "1_1") (pintype "passive"))
    )
    (net (code "103") (name "Net-(D1-A)") (class "Default")
      (node (ref "C3") (pin "1") (pinfunction "1_1") (pintype "passive"))
      (node (ref "D1") (pin "1") (pinfunction "A_1") (pintype "passive"))
      (node (ref "E4") (pin "2") (pinfunction "K_2") (pintype "passive"))
      (node (ref "IC1") (pin "4") (pinfunction "GND_4") (pintype "passive"))
      (node (ref "L3") (pin "1") (pinfunction "1_1") (pintype "passive"))
      (node (ref "R6") (pin "1") (pinfunction "1_1") (pintype "passive"))
    )
    (net (code "104") (name "Net-(D1-K)") (class "Default")
      (node (ref "D1") (pin "2") (pinfunction "K_2") (pintype "passive"))
      (node (ref "IC1") (pin "2") (pinfunction "SWE_2") (pintype "passive"))
      (node (ref "L2") (pin "2") (pinfunction "2_2") (pintype "passive"))
    )
    (net (code "105") (name "Net-(D2-A)") (class "Default")
      (node (ref "D2") (pin "1") (pinfunction "A_1") (pintype "passive"))
      (node (ref "D3") (pin "2") (pinfunction "K_2") (pintype "passive"))
      (node (ref "R25") (pin "2") (pinfunction "2_2") (pintype "passive"))
      (node (ref "R27") (pin "2") (pinfunction "2_2") (pintype "passive"))
      (node (ref "U4") (pin "3") (pinfunction "+IN1_3") (pintype "power_in"))
    )
    (net (code "106") (name "Net-(D2-K)") (class "Default")
      (node (ref "D2") (pin "2") (pinfunction "K_2") (pintype "passive"))
      (node (ref "D3") (pin "1") (pinfunction "A_1") (pintype "passive"))
      (node (ref "R15") (pin "1") (pinfunction "1_1") (pintype "passive"))
      (node (ref "R20") (pin "1") (pinfunction "1_1") (pintype "passive"))
      (node (ref "U4") (pin "4") (pinfunction "-IN1_4") (pintype "power_in"))
    )
    (net (code "107") (name "Net-(ETHNET1-LED(G)_A)") (class "Default")
      (node (ref "ETHNET1") (pin "9") (pinfunction "LED(G)_A_9") (pintype "passive"))
      (node (ref "R19") (pin "1") (pinfunction "1_1") (pintype "passive"))
    )
    (net (code "108") (name "Net-(ETHNET1-LED(Y)_A)") (class "Default")
      (node (ref "ETHNET1") (pin "12") (pinfunction "LED(Y)_A_12") (pintype "passive"))
      (node (ref "R18") (pin "1") (pinfunction "1_1") (pintype "passive"))
    )
    (net (code "109") (name "Net-(IC1-CII)") (class "Default")
      (node (ref "IC1") (pin "5") (pinfunction "CII_5") (pintype "passive"))
      (node (ref "R6") (pin "2") (pinfunction "2_2") (pintype "passive"))
      (node (ref "R7") (pin "2") (pinfunction "2_2") (pintype "passive"))
    )
    (net (code "110") (name "Net-(IC1-DEC)") (class "Default")
      (node (ref "IC1") (pin "1") (pinfunction "SWC_1") (pintype "passive"))
      (node (ref "IC1") (pin "7") (pinfunction "IPK_7") (pintype "passive"))
      (node (ref "IC1") (pin "8") (pinfunction "DEC_8") (pintype "passive"))
      (node (ref "R3") (pin "2") (pinfunction "2_2") (pintype "passive"))
    )
    (net (code "111") (name "Net-(IC1-TC)") (class "Default")
      (node (ref "C3") (pin "2") (pinfunction "2_2") (pintype "passive"))
      (node (ref "IC1") (pin "3") (pinfunction "TC_3") (pintype "passive"))
    )
    (net (code "112") (name "Net-(LED1-A)") (class "Default")
      (node (ref "LED1") (pin "1") (pinfunction "A_1") (pintype "passive"))
      (node (ref "R") (pin "1") (pinfunction "1_1") (pintype "passive"))
    )
    (net (code "113") (name "Net-(P1-Signal)") (class "Default")
      (node (ref "P1") (pin "1") (pinfunction "Signal_1") (pintype "input"))
      (node (ref "R25") (pin "1") (pinfunction "1_1") (pintype "passive"))
    )
    (net (code "114") (name "Net-(P2-Signal)") (class "Default")
      (node (ref "P2") (pin "1") (pinfunction "Signal_1") (pintype "input"))
      (node (ref "R37") (pin "1") (pinfunction "1_1") (pintype "passive"))
    )
    (net (code "115") (name "Net-(U1-COL)") (class "Default")
      (node (ref "R9") (pin "2") (pinfunction "2_2") (pintype "passive"))
      (node (ref "U1") (pin "1") (pinfunction "COL_1") (pintype "passive"))
    )
    (net (code "116") (name "Net-(U1-CRS)") (class "Default")
      (node (ref "R8") (pin "2") (pinfunction "2_2") (pintype "passive"))
      (node (ref "U1") (pin "23") (pinfunction "CRS_23") (pintype "passive"))
    )
    (net (code "117") (name "Net-(U1-LED1{slash}AD1)") (class "Default")
      (node (ref "R11") (pin "2") (pinfunction "2_2") (pintype "passive"))
      (node (ref "U1") (pin "10") (pinfunction "LED1/AD1_10") (pintype "passive"))
    )
    (net (code "118") (name "Net-(U1-LED2{slash}AD2)") (class "Default")
      (node (ref "R12") (pin "2") (pinfunction "2_2") (pintype "passive"))
      (node (ref "U1") (pin "12") (pinfunction "LED2/AD2_12") (pintype "passive"))
    )
    (net (code "119") (name "Net-(U1-LED4{slash}AD4)") (class "Default")
      (node (ref "R14") (pin "2") (pinfunction "2_2") (pintype "passive"))
      (node (ref "U1") (pin "15") (pinfunction "LED4/AD4_15") (pintype "passive"))
    )
    (net (code "120") (name "Net-(U1-RTSET)") (class "Default")
      (node (ref "R4") (pin "1") (pinfunction "1_1") (pintype "passive"))
      (node (ref "U1") (pin "28") (pinfunction "RTSET_28") (pintype "passive"))
    )
    (net (code "121") (name "Net-(U1-X1)") (class "Default")
      (node (ref "C14") (pin "1") (pinfunction "1_1") (pintype "passive"))
      (node (ref "U1") (pin "46") (pinfunction "X1_46") (pintype "passive"))
      (node (ref "X1") (pin "1") (pinfunction "1_1") (pintype "passive"))
    )
    (net (code "122") (name "Net-(U1-X2)") (class "Default")
      (node (ref "C13") (pin "1") (pinfunction "1_1") (pintype "passive"))
      (node (ref "U1") (pin "47") (pinfunction "X2_47") (pintype "passive"))
      (node (ref "X1") (pin "3") (pinfunction "3_3") (pintype "passive"))
    )
    (net (code "123") (name "Net-(U2A--IN1)") (class "Default")
      (node (ref "R16") (pin "2") (pinfunction "2_2") (pintype "passive"))
      (node (ref "U2") (pin "1") (pinfunction "OUT1_1") (pintype "power_in"))
      (node (ref "U2") (pin "2") (pinfunction "-IN1_2") (pintype "power_in"))
    )
    (net (code "124") (name "Net-(U2B--IN1)") (class "Default")
      (node (ref "R16") (pin "1") (pinfunction "1_1") (pintype "passive"))
      (node (ref "R17") (pin "2") (pinfunction "2_2") (pintype "passive"))
      (node (ref "U2") (pin "6") (pinfunction "-IN1_6") (pintype "power_in"))
    )
    (net (code "125") (name "Net-(U3-CLK)") (class "Default")
      (node (ref "R28") (pin "1") (pinfunction "1_1") (pintype "passive"))
      (node (ref "U3") (pin "15") (pinfunction "CLK_15") (pintype "power_in"))
    )
    (net (code "126") (name "Net-(U3-DRVDD)") (class "Default")
      (node (ref "C23") (pin "1") (pinfunction "1_1") (pintype "passive"))
      (node (ref "L4") (pin "1") (pinfunction "1_1") (pintype "passive"))
      (node (ref "U3") (pin "2") (pinfunction "DRVDD_2") (pintype "power_in"))
    )
    (net (code "127") (name "Net-(U3-REFBF)") (class "Default")
      (node (ref "C15") (pin "2") (pinfunction "2_2") (pintype "passive"))
      (node (ref "C17") (pin "2") (pinfunction "2_2") (pintype "passive"))
      (node (ref "C18") (pin "2") (pinfunction "2_2") (pintype "passive"))
      (node (ref "U3") (pin "24") (pinfunction "REFBF_24") (pintype "power_in"))
    )
    (net (code "128") (name "Net-(U3-REFTF)") (class "Default")
      (node (ref "C17") (pin "1") (pinfunction "1_1") (pintype "passive"))
      (node (ref "C18") (pin "1") (pinfunction "1_1") (pintype "passive"))
      (node (ref "C19") (pin "1") (pinfunction "1_1") (pintype "passive"))
      (node (ref "U3") (pin "22") (pinfunction "REFTF_22") (pintype "power_in"))
    )
    (net (code "129") (name "Net-(U4-OUT1)") (class "Default")
      (node (ref "R20") (pin "2") (pinfunction "2_2") (pintype "passive"))
      (node (ref "R24") (pin "1") (pinfunction "1_1") (pintype "passive"))
      (node (ref "U4") (pin "1") (pinfunction "OUT1_1") (pintype "power_in"))
    )
    (net (code "130") (name "Net-(U6-CLK)") (class "Default")
      (node (ref "R36") (pin "1") (pinfunction "1_1") (pintype "passive"))
      (node (ref "U6") (pin "28") (pinfunction "CLK_28") (pintype "power_in"))
    )
    (net (code "131") (name "Net-(U6-COMP1)") (class "Default")
      (node (ref "C33") (pin "2") (pinfunction "2_2") (pintype "passive"))
      (node (ref "U6") (pin "19") (pinfunction "COMP1_19") (pintype "power_in"))
    )
    (net (code "132") (name "Net-(U6-COMP2)") (class "Default")
      (node (ref "C34") (pin "2") (pinfunction "2_2") (pintype "passive"))
      (node (ref "U6") (pin "23") (pinfunction "COMP2_23") (pintype "power_in"))
    )
    (net (code "133") (name "Net-(U6-FSADJ)") (class "Default")
      (node (ref "R38") (pin "1") (pinfunction "1_1") (pintype "passive"))
      (node (ref "U6") (pin "18") (pinfunction "FSADJ_18") (pintype "power_in"))
    )
    (net (code "134") (name "Net-(U6-IOUTA)") (class "Default")
      (node (ref "C25") (pin "2") (pinfunction "2_2") (pintype "passive"))
      (node (ref "L6") (pin "1") (pinfunction "1_1") (pintype "passive"))
      (node (ref "R29") (pin "2") (pinfunction "2_2") (pintype "passive"))
      (node (ref "U6") (pin "22") (pinfunction "IOUTA_22") (pintype "power_in"))
    )
    (net (code "135") (name "Net-(U6-IOUTB)") (class "Default")
      (node (ref "C29") (pin "2") (pinfunction "2_2") (pintype "passive"))
      (node (ref "L9") (pin "2") (pinfunction "2_2") (pintype "passive"))
      (node (ref "R33") (pin "1") (pinfunction "1_1") (pintype "passive"))
      (node (ref "U6") (pin "21") (pinfunction "IOUTB_21") (pintype "power_in"))
    )
    (net (code "136") (name "Net-(U6-REFIO)") (class "Default")
      (node (ref "C35") (pin "2") (pinfunction "2_2") (pintype "passive"))
      (node (ref "U6") (pin "17") (pinfunction "REFIO_17") (pintype "power_in"))
    )
    (net (code "137") (name "Net-(U7A-OUT1)") (class "Default")
      (node (ref "R39") (pin "2") (pinfunction "2_2") (pintype "passive"))
      (node (ref "R40") (pin "1") (pinfunction "1_1") (pintype "passive"))
      (node (ref "U7") (pin "1") (pinfunction "OUT1_1") (pintype "power_in"))
    )
    (net (code "138") (name "Net-(U7B--IN1)") (class "Default")
      (node (ref "R39") (pin "1") (pinfunction "1_1") (pintype "passive"))
      (node (ref "U7") (pin "6") (pinfunction "-IN1_6") (pintype "power_in"))
      (node (ref "W1") (pin "3") (pinfunction "3_3") (pintype "passive"))
    )
    (net (code "139") (name "Net-(U7B-OUT2)") (class "Default")
      (node (ref "R37") (pin "2") (pinfunction "2_2") (pintype "passive"))
      (node (ref "U7") (pin "7") (pinfunction "OUT2_7") (pintype "power_in"))
      (node (ref "W1") (pin "2") (pinfunction "W_2") (pintype "passive"))
    )
    (net (code "140") (name "SDGND") (class "Default")
      (node (ref "C37") (pin "1") (pinfunction "1_1") (pintype "passive"))
      (node (ref "C38") (pin "1") (pinfunction "1_1") (pintype "passive"))
      (node (ref "C39") (pin "1") (pinfunction "1_1") (pintype "passive"))
      (node (ref "C40") (pin "1") (pinfunction "1_1") (pintype "passive"))
      (node (ref "C41") (pin "1") (pinfunction "1_1") (pintype "passive"))
      (node (ref "C42") (pin "1") (pinfunction "1_1") (pintype "passive"))
      (node (ref "C43") (pin "1") (pinfunction "1_1") (pintype "passive"))
      (node (ref "C44") (pin "1") (pinfunction "1_1") (pintype "passive"))
      (node (ref "JP7") (pin "2") (pinfunction "2_2") (pintype "passive"))
      (node (ref "JP7") (pin "4") (pinfunction "4_4") (pintype "passive"))
      (node (ref "U5") (pin "12") (pinfunction "VSSQ1_12") (pintype "power_in"))
      (node (ref "U5") (pin "28") (pinfunction "VSS2_28") (pintype "power_in"))
      (node (ref "U5") (pin "41") (pinfunction "VSS0_41") (pintype "power_in"))
      (node (ref "U5") (pin "46") (pinfunction "VSSQ2_46") (pintype "power_in"))
      (node (ref "U5") (pin "52") (pinfunction "VSSQ3_52") (pintype "power_in"))
      (node (ref "U5") (pin "54") (pinfunction "VSS1_54") (pintype "power_in"))
      (node (ref "U5") (pin "6") (pinfunction "VSSQ0_6") (pintype "power_in"))
    )
    (net (code "141") (name "SDVCC3.3") (class "Default")
      (node (ref "C37") (pin "2") (pinfunction "2_2") (pintype "passive"))
      (node (ref "C38") (pin "2") (pinfunction "2_2") (pintype "passive"))
      (node (ref "C39") (pin "2") (pinfunction "2_2") (pintype "passive"))
      (node (ref "C40") (pin "2") (pinfunction "2_2") (pintype "passive"))
      (node (ref "C41") (pin "2") (pinfunction "2_2") (pintype "passive"))
      (node (ref "C42") (pin "2") (pinfunction "2_2") (pintype "passive"))
      (node (ref "C43") (pin "2") (pinfunction "2_2") (pintype "passive"))
      (node (ref "C44") (pin "2") (pinfunction "2_2") (pintype "passive"))
      (node (ref "JP7") (pin "1") (pinfunction "1_1") (pintype "passive"))
      (node (ref "U5") (pin "1") (pinfunction "VDD0_1") (pintype "power_in"))
      (node (ref "U5") (pin "14") (pinfunction "VDD1_14") (pintype "power_in"))
      (node (ref "U5") (pin "27") (pinfunction "VDD2_27") (pintype "power_in"))
      (node (ref "U5") (pin "3") (pinfunction "VDDQ0_3") (pintype "power_in"))
      (node (ref "U5") (pin "43") (pinfunction "VDDQ2_43") (pintype "power_in"))
      (node (ref "U5") (pin "49") (pinfunction "VDDQ3_49") (pintype "power_in"))
      (node (ref "U5") (pin "9") (pinfunction "VDDQ1_9") (pintype "power_in"))
    )
    (net (code "142") (name "VCC") (class "Default")
      (node (ref "C1") (pin "2") (pinfunction "2_2") (pintype "passive"))
      (node (ref "E3") (pin "1") (pinfunction "A_1") (pintype "passive"))
      (node (ref "IC1") (pin "6") (pinfunction "VCC_6") (pintype "passive"))
      (node (ref "JP1") (pin "1") (pinfunction "1_1") (pintype "passive"))
      (node (ref "JP1") (pin "3") (pinfunction "3_3") (pintype "passive"))
      (node (ref "L1") (pin "1") (pinfunction "1_1") (pintype "passive"))
      (node (ref "R") (pin "2") (pinfunction "2_2") (pintype "passive"))
      (node (ref "R3") (pin "1") (pinfunction "1_1") (pintype "passive"))
      (node (ref "V1") (pin "3") (pinfunction "Vin_3") (pintype "passive"))
    )
    (net (code "143") (name "unconnected-(ETHNET1-NC-Pad7)") (class "Default")
      (node (ref "ETHNET1") (pin "7") (pinfunction "NC_7") (pintype "passive"))
    )
    (net (code "144") (name "unconnected-(JP1-Pad15)") (class "Default")
      (node (ref "JP1") (pin "15") (pinfunction "15_15") (pintype "passive+no_connect"))
    )
    (net (code "145") (name "unconnected-(U1-NC-Pad27)") (class "Default")
      (node (ref "U1") (pin "27") (pinfunction "NC_27") (pintype "passive+no_connect"))
    )
    (net (code "146") (name "unconnected-(U6-SLEEP-Pad15)") (class "Default")
      (node (ref "U6") (pin "15") (pinfunction "SLEEP_15") (pintype "power_in+no_connect"))
    )
    (net (code "147") (name "unconnected-(W1-Pad1)") (class "Default")
      (node (ref "W1") (pin "1") (pinfunction "1_1") (pintype "passive"))
    )
  )
)
